# Hbridge_new.net
KiCad netlist of a schematic drawn in EAGLE
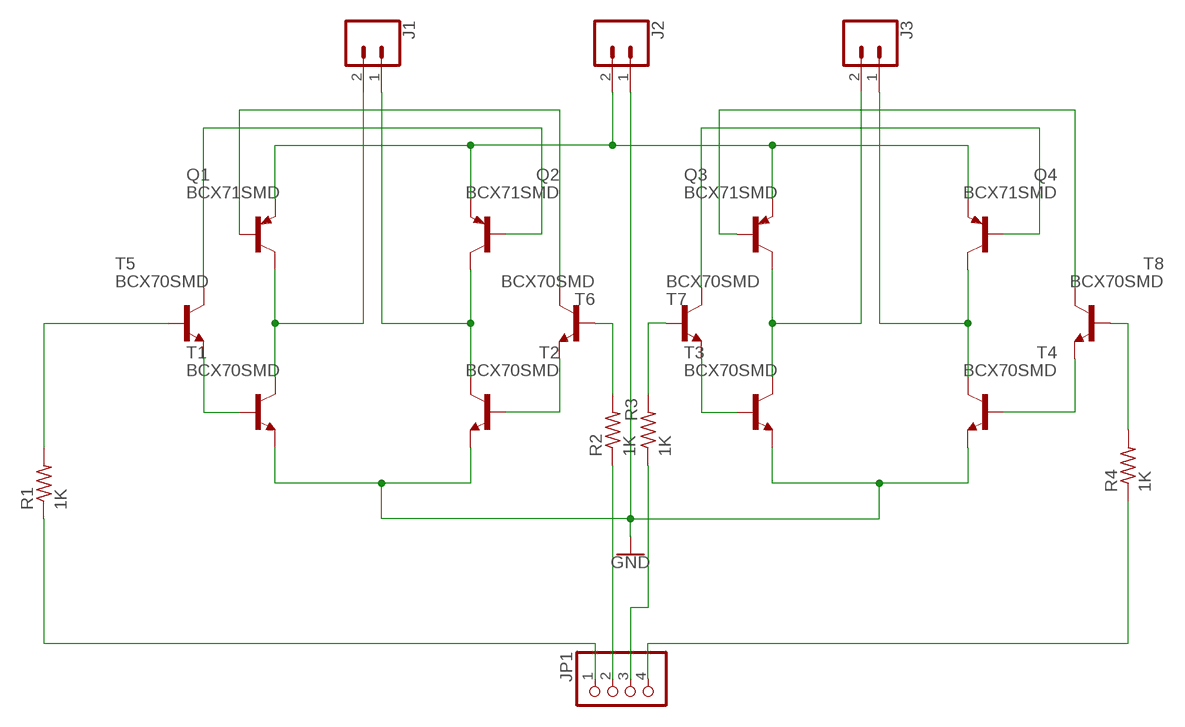
[diagram p0: schematic, sheet 1]

(export (version "E")
  (design (tool "Eeschema 10.0.6"))
  (components
    (comp (ref "J1")
      (value "CONN_02-JST-2MM-SMT")
      (footprint "eagle-import:JST-2-SMD")
      (libsource (lib "eagle-import") (part "CONN_02-JST-2MM-SMT"))
    )
    (comp (ref "J2")
      (value "CONN_02-JST-2MM-SMT")
      (footprint "eagle-import:JST-2-SMD")
      (libsource (lib "eagle-import") (part "CONN_02-JST-2MM-SMT"))
    )
    (comp (ref "J3")
      (value "CONN_02-JST-2MM-SMT")
      (footprint "eagle-import:JST-2-SMD")
      (libsource (lib "eagle-import") (part "CONN_02-JST-2MM-SMT"))
    )
    (comp (ref "JP1")
      (value "PINHD-1X4")
      (footprint "eagle-import:1X04")
      (libsource (lib "eagle-import") (part "PINHD-1X4"))
    )
    (comp (ref "Q1")
      (value "BCX71SMD")
      (footprint "eagle-import:SOT23")
      (libsource (lib "eagle-import") (part "BCX71SMD"))
    )
    (comp (ref "Q2")
      (value "BCX71SMD")
      (footprint "eagle-import:SOT23")
      (libsource (lib "eagle-import") (part "BCX71SMD"))
    )
    (comp (ref "Q3")
      (value "BCX71SMD")
      (footprint "eagle-import:SOT23")
      (libsource (lib "eagle-import") (part "BCX71SMD"))
    )
    (comp (ref "Q4")
      (value "BCX71SMD")
      (footprint "eagle-import:SOT23")
      (libsource (lib "eagle-import") (part "BCX71SMD"))
    )
    (comp (ref "R1")
      (value "1K")
      (footprint "eagle-import:M0805")
      (libsource (lib "eagle-import") (part "R-US_M0805"))
    )
    (comp (ref "R2")
      (value "1K")
      (footprint "eagle-import:M0805")
      (libsource (lib "eagle-import") (part "R-US_M0805"))
    )
    (comp (ref "R3")
      (value "1K")
      (footprint "eagle-import:M0805")
      (libsource (lib "eagle-import") (part "R-US_M0805"))
    )
    (comp (ref "R4")
      (value "1K")
      (footprint "eagle-import:M0805")
      (libsource (lib "eagle-import") (part "R-US_M0805"))
    )
    (comp (ref "T1")
      (value "BCX70SMD")
      (footprint "eagle-import:SOT23")
      (libsource (lib "eagle-import") (part "BCX70SMD"))
    )
    (comp (ref "T2")
      (value "BCX70SMD")
      (footprint "eagle-import:SOT23")
      (libsource (lib "eagle-import") (part "BCX70SMD"))
    )
    (comp (ref "T3")
      (value "BCX70SMD")
      (footprint "eagle-import:SOT23")
      (libsource (lib "eagle-import") (part "BCX70SMD"))
    )
    (comp (ref "T4")
      (value "BCX70SMD")
      (footprint "eagle-import:SOT23")
      (libsource (lib "eagle-import") (part "BCX70SMD"))
    )
    (comp (ref "T5")
      (value "BCX70SMD")
      (footprint "eagle-import:SOT23")
      (libsource (lib "eagle-import") (part "BCX70SMD"))
    )
    (comp (ref "T6")
      (value "BCX70SMD")
      (footprint "eagle-import:SOT23")
      (libsource (lib "eagle-import") (part "BCX70SMD"))
    )
    (comp (ref "T7")
      (value "BCX70SMD")
      (footprint "eagle-import:SOT23")
      (libsource (lib "eagle-import") (part "BCX70SMD"))
    )
    (comp (ref "T8")
      (value "BCX70SMD")
      (footprint "eagle-import:SOT23")
      (libsource (lib "eagle-import") (part "BCX70SMD"))
    )
  )
  (nets
    (net (code "1") (name "GND") (class "Default")
      (node (ref "J2") (pin "1") (pinfunction "2_1") (pintype "passive"))
      (node (ref "T1") (pin "2") (pinfunction "E_2") (pintype "passive"))
      (node (ref "T2") (pin "2") (pinfunction "E_2") (pintype "passive"))
      (node (ref "T3") (pin "2") (pinfunction "E_2") (pintype "passive"))
      (node (ref "T4") (pin "2") (pinfunction "E_2") (pintype "passive"))
    )
    (net (code "2") (name "Net-(J1-1)") (class "Default")
      (node (ref "J1") (pin "2") (pinfunction "1_2") (pintype "passive"))
      (node (ref "Q1") (pin "3") (pinfunction "C_3") (pintype "passive"))
      (node (ref "T1") (pin "3") (pinfunction "C_3") (pintype "passive"))
    )
    (net (code "3") (name "Net-(J1-2)") (class "Default")
      (node (ref "J1") (pin "1") (pinfunction "2_1") (pintype "passive"))
      (node (ref "Q2") (pin "3") (pinfunction "C_3") (pintype "passive"))
      (node (ref "T2") (pin "3") (pinfunction "C_3") (pintype "passive"))
    )
    (net (code "4") (name "Net-(J2-1)") (class "Default")
      (node (ref "J2") (pin "2") (pinfunction "1_2") (pintype "passive"))
      (node (ref "Q1") (pin "2") (pinfunction "E_2") (pintype "passive"))
      (node (ref "Q2") (pin "2") (pinfunction "E_2") (pintype "passive"))
      (node (ref "Q3") (pin "2") (pinfunction "E_2") (pintype "passive"))
      (node (ref "Q4") (pin "2") (pinfunction "E_2") (pintype "passive"))
    )
    (net (code "5") (name "Net-(J3-1)") (class "Default")
      (node (ref "J3") (pin "2") (pinfunction "1_2") (pintype "passive"))
      (node (ref "Q3") (pin "3") (pinfunction "C_3") (pintype "passive"))
      (node (ref "T3") (pin "3") (pinfunction "C_3") (pintype "passive"))
    )
    (net (code "6") (name "Net-(J3-2)") (class "Default")
      (node (ref "J3") (pin "1") (pinfunction "2_1") (pintype "passive"))
      (node (ref "Q4") (pin "3") (pinfunction "C_3") (pintype "passive"))
      (node (ref "T4") (pin "3") (pinfunction "C_3") (pintype "passive"))
    )
    (net (code "7") (name "Net-(JP1-Pad1)") (class "Default")
      (node (ref "JP1") (pin "1") (pinfunction "1_1") (pintype "passive"))
      (node (ref "R1") (pin "1") (pinfunction "1_1") (pintype "passive"))
    )
    (net (code "8") (name "Net-(JP1-Pad2)") (class "Default")
      (node (ref "JP1") (pin "2") (pinfunction "2_2") (pintype "passive"))
      (node (ref "R2") (pin "1") (pinfunction "1_1") (pintype "passive"))
    )
    (net (code "9") (name "Net-(JP1-Pad3)") (class "Default")
      (node (ref "JP1") (pin "3") (pinfunction "3_3") (pintype "passive"))
      (node (ref "R3") (pin "1") (pinfunction "1_1") (pintype "passive"))
    )
    (net (code "10") (name "Net-(JP1-Pad4)") (class "Default")
      (node (ref "JP1") (pin "4") (pinfunction "4_4") (pintype "passive"))
      (node (ref "R4") (pin "1") (pinfunction "1_1") (pintype "passive"))
    )
    (net (code "11") (name "Net-(Q1-B)") (class "Default")
      (node (ref "Q1") (pin "1") (pinfunction "B_1") (pintype "passive"))
      (node (ref "T6") (pin "3") (pinfunction "C_3") (pintype "passive"))
    )
    (net (code "12") (name "Net-(Q2-B)") (class "Default")
      (node (ref "Q2") (pin "1") (pinfunction "B_1") (pintype "passive"))
      (node (ref "T5") (pin "3") (pinfunction "C_3") (pintype "passive"))
    )
    (net (code "13") (name "Net-(Q3-B)") (class "Default")
      (node (ref "Q3") (pin "1") (pinfunction "B_1") (pintype "passive"))
      (node (ref "T8") (pin "3") (pinfunction "C_3") (pintype "passive"))
    )
    (net (code "14") (name "Net-(Q4-B)") (class "Default")
      (node (ref "Q4") (pin "1") (pinfunction "B_1") (pintype "passive"))
      (node (ref "T7") (pin "3") (pinfunction "C_3") (pintype "passive"))
    )
    (net (code "15") (name "Net-(T1-B)") (class "Default")
      (node (ref "T1") (pin "1") (pinfunction "B_1") (pintype "passive"))
      (node (ref "T5") (pin "2") (pinfunction "E_2") (pintype "passive"))
    )
    (net (code "16") (name "Net-(T2-B)") (class "Default")
      (node (ref "T2") (pin "1") (pinfunction "B_1") (pintype "passive"))
      (node (ref "T6") (pin "2") (pinfunction "E_2") (pintype "passive"))
    )
    (net (code "17") (name "Net-(T3-B)") (class "Default")
      (node (ref "T3") (pin "1") (pinfunction "B_1") (pintype "passive"))
      (node (ref "T7") (pin "2") (pinfunction "E_2") (pintype "passive"))
    )
    (net (code "18") (name "Net-(T4-B)") (class "Default")
      (node (ref "T4") (pin "1") (pinfunction "B_1") (pintype "passive"))
      (node (ref "T8") (pin "2") (pinfunction "E_2") (pintype "passive"))
    )
    (net (code "19") (name "Net-(T5-B)") (class "Default")
      (node (ref "R1") (pin "2") (pinfunction "2_2") (pintype "passive"))
      (node (ref "T5") (pin "1") (pinfunction "B_1") (pintype "passive"))
    )
    (net (code "20") (name "Net-(T6-B)") (class "Default")
      (node (ref "R2") (pin "2") (pinfunction "2_2") (pintype "passive"))
      (node (ref "T6") (pin "1") (pinfunction "B_1") (pintype "passive"))
    )
    (net (code "21") (name "Net-(T7-B)") (class "Default")
      (node (ref "R3") (pin "2") (pinfunction "2_2") (pintype "passive"))
      (node (ref "T7") (pin "1") (pinfunction "B_1") (pintype "passive"))
    )
    (net (code "22") (name "Net-(T8-B)") (class "Default")
      (node (ref "R4") (pin "2") (pinfunction "2_2") (pintype "passive"))
      (node (ref "T8") (pin "1") (pinfunction "B_1") (pintype "passive"))
    )
  )
)
